# MCU.net
KiCad netlist of a schematic drawn in EasyEDA Pro
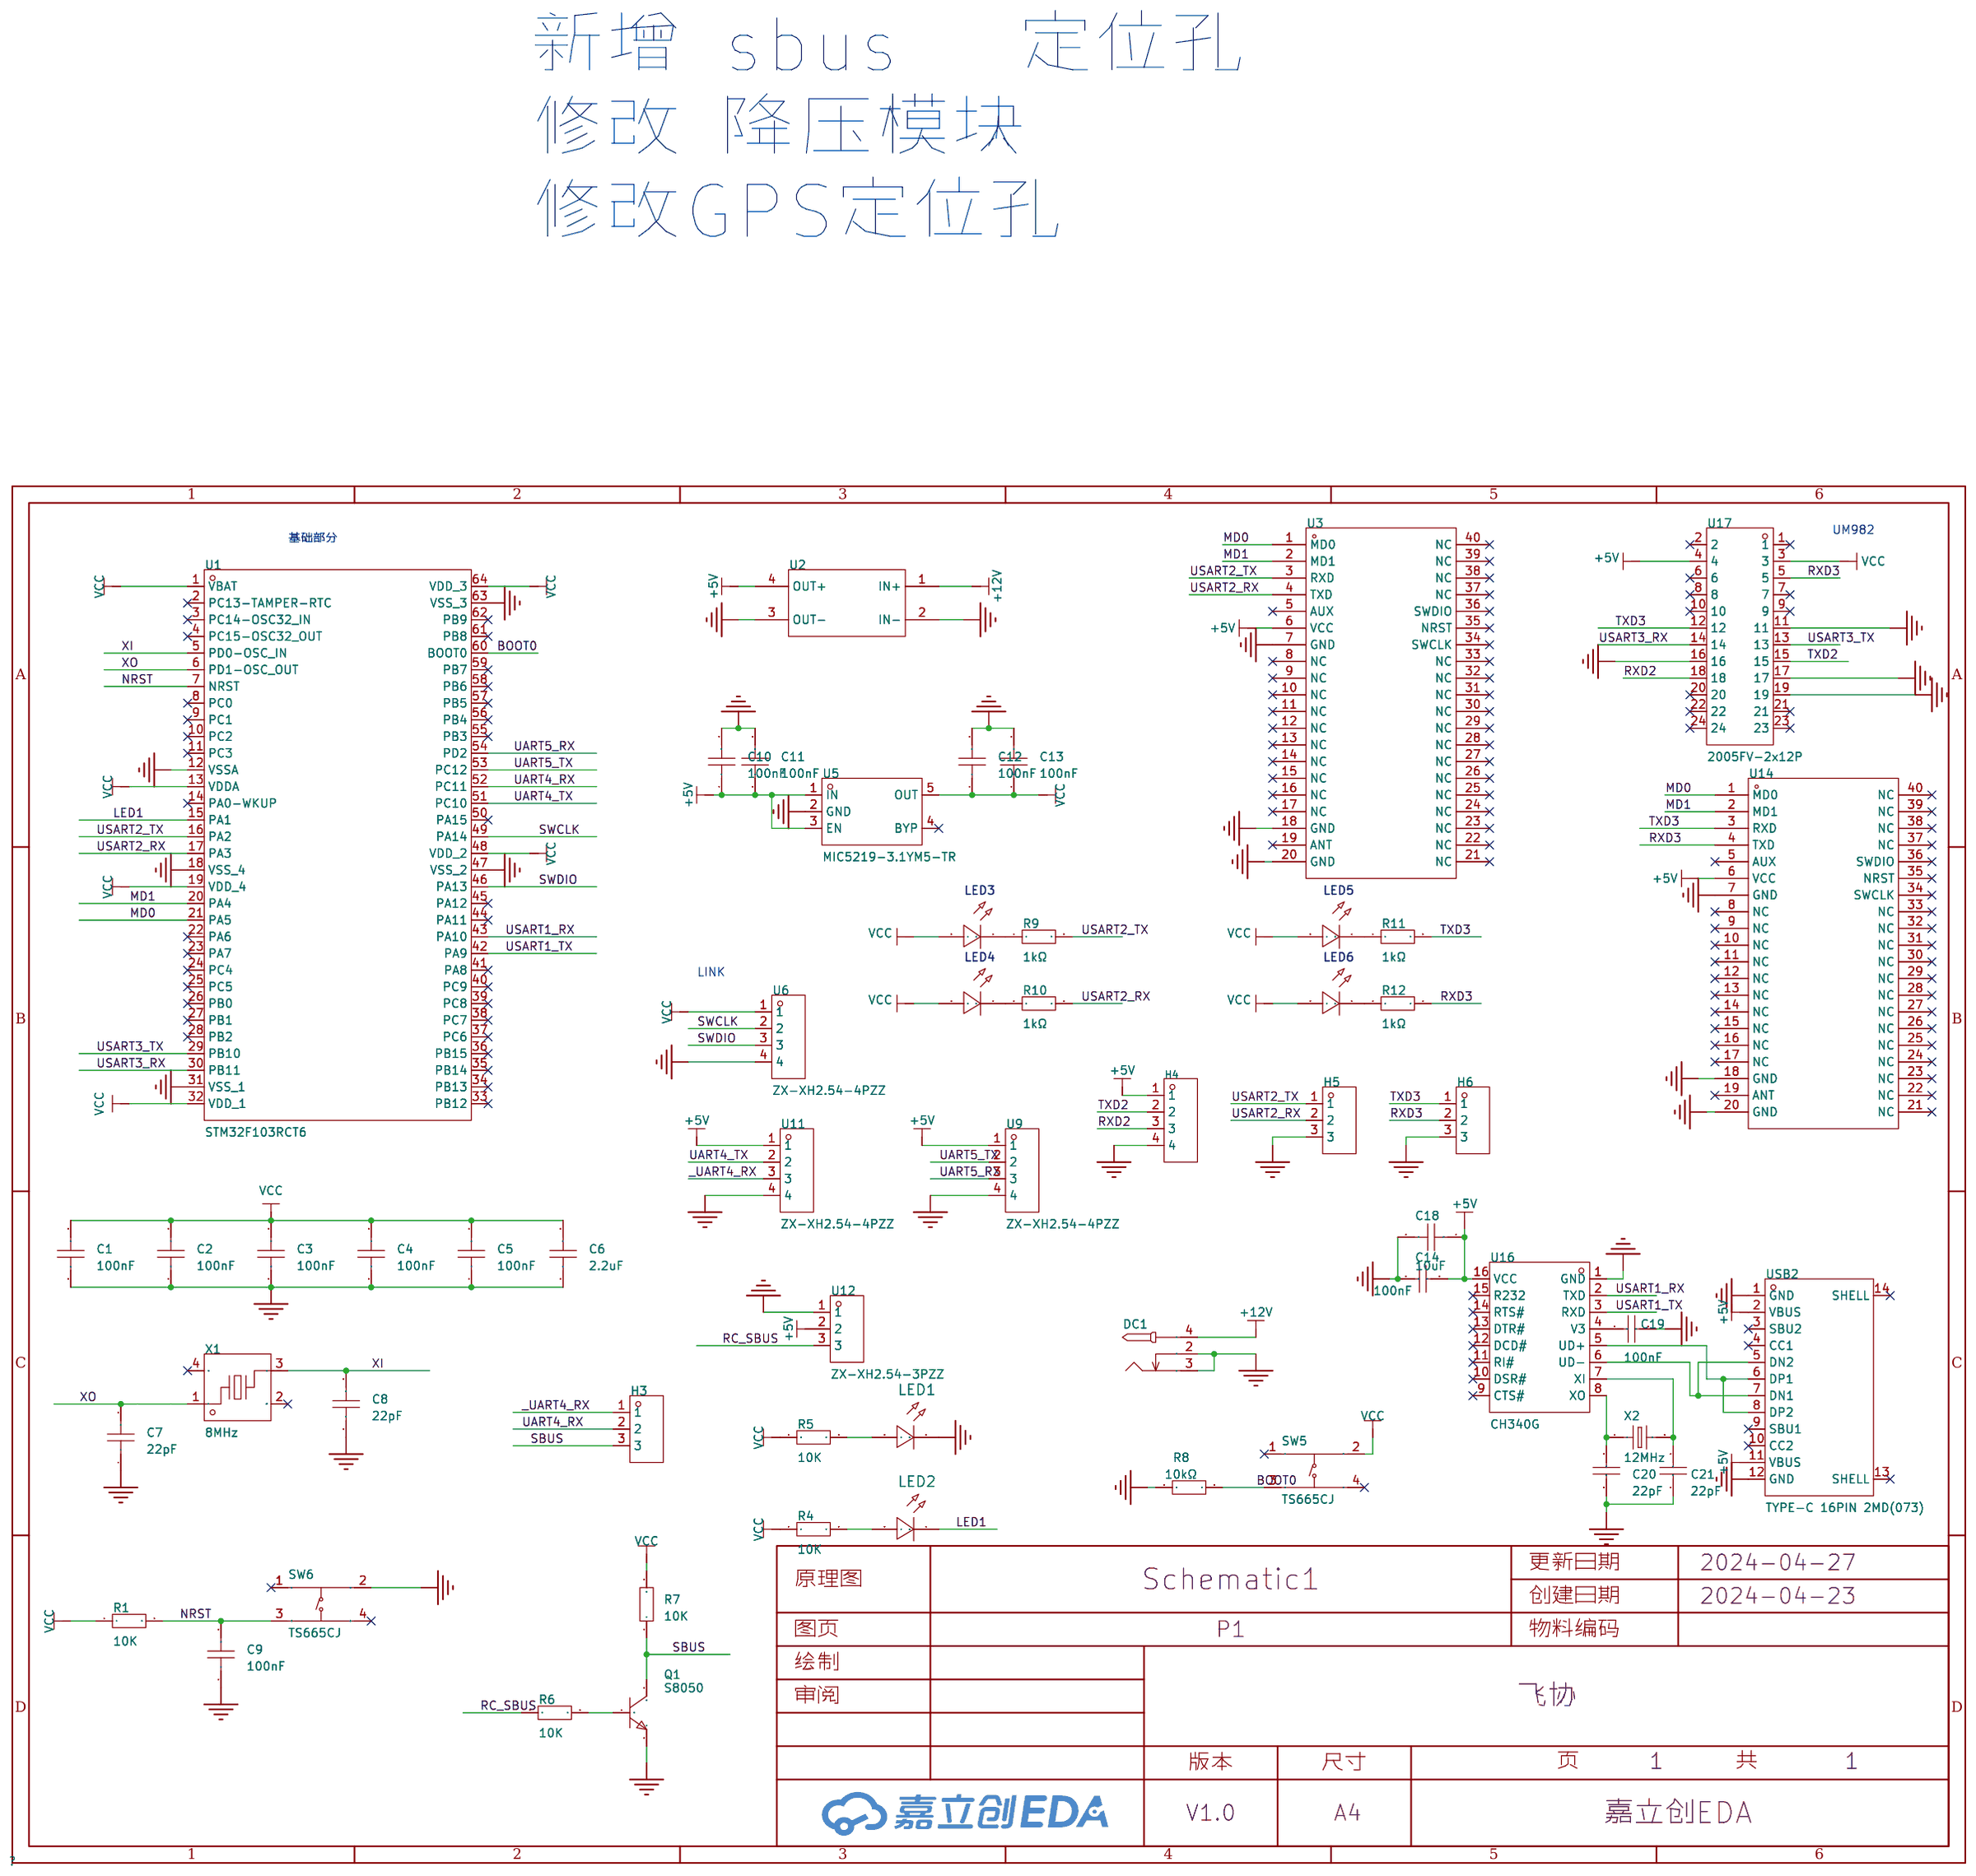
[diagram p0: schematic sheet]

(export (version "E")
  (design (tool "Eeschema 10.0.6"))
  (components
    (comp (ref "C1")
      (value "100nF")
      (footprint "easyedapro:C0603")
      (libsource (lib "easyedapro") (part "CapAcitance"))
    )
    (comp (ref "C2")
      (value "100nF")
      (footprint "easyedapro:C0603")
      (libsource (lib "easyedapro") (part "CapAcitance"))
    )
    (comp (ref "C3")
      (value "100nF")
      (footprint "easyedapro:C0603")
      (libsource (lib "easyedapro") (part "CapAcitance"))
    )
    (comp (ref "C4")
      (value "100nF")
      (footprint "easyedapro:C0603")
      (libsource (lib "easyedapro") (part "CapAcitance"))
    )
    (comp (ref "C5")
      (value "100nF")
      (footprint "easyedapro:C0603")
      (libsource (lib "easyedapro") (part "CapAcitance"))
    )
    (comp (ref "C6")
      (value "2.2uF")
      (footprint "easyedapro:C0603")
      (libsource (lib "easyedapro") (part "CapAcitance"))
    )
    (comp (ref "C7")
      (value "22pF")
      (footprint "easyedapro:C0603")
      (libsource (lib "easyedapro") (part "CapAcitance"))
    )
    (comp (ref "C8")
      (value "22pF")
      (footprint "easyedapro:C0603")
      (libsource (lib "easyedapro") (part "CapAcitance"))
    )
    (comp (ref "C9")
      (value "100nF")
      (footprint "easyedapro:C0603")
      (libsource (lib "easyedapro") (part "CapAcitance"))
    )
    (comp (ref "C10")
      (value "100nF")
      (footprint "easyedapro:C0603")
      (libsource (lib "easyedapro") (part "CapAcitance"))
    )
    (comp (ref "C11")
      (value "100nF")
      (footprint "easyedapro:C0603")
      (libsource (lib "easyedapro") (part "CapAcitance"))
    )
    (comp (ref "C12")
      (value "100nF")
      (footprint "easyedapro:C0603")
      (libsource (lib "easyedapro") (part "CapAcitance"))
    )
    (comp (ref "C13")
      (value "100nF")
      (footprint "easyedapro:C0603")
      (libsource (lib "easyedapro") (part "CapAcitance"))
    )
    (comp (ref "C14")
      (value "100nF")
      (footprint "easyedapro:C0603")
      (description "容值:100nF;精度:±10%;额定电压:50V;材质(温度系数):X7R;")
      (fields (field (name "Manufacturer Part") "0603B104K500NT") (field (name "Manufacturer") "FH(风华)"))
      (libsource (lib "easyedapro") (part "0603B104K500NT"))
    )
    (comp (ref "C18")
      (value "10uF")
      (footprint "easyedapro:C0603")
      (description "容值:10uF;精度:±20%;额定电压:25V;材质(温度系数):X5R;")
      (fields
        (field (name "Manufacturer Part") "CL10A106MA8NRNC")
        (field (name "Manufacturer") "SAMSUNG(三星)")
      )
      (libsource (lib "easyedapro") (part "CL10A106MA8NRNC"))
    )
    (comp (ref "C19")
      (value "100nF")
      (footprint "easyedapro:C0603")
      (description "容值:100nF;精度:±10%;额定电压:50V;材质(温度系数):X7R;")
      (fields (field (name "Manufacturer Part") "0603B104K500NT") (field (name "Manufacturer") "FH(风华)"))
      (libsource (lib "easyedapro") (part "0603B104K500NT"))
    )
    (comp (ref "C20")
      (value "22pF")
      (footprint "easyedapro:C0603")
      (description "容值:22pF;精度:±5%;额定电压:50V;材质(温度系数):NP0;")
      (fields
        (field (name "Manufacturer Part") "CC0603JRNPO9BN220")
        (field (name "Manufacturer") "YAGEO(国巨)")
      )
      (libsource (lib "easyedapro") (part "CC0603JRNPO9BN220"))
    )
    (comp (ref "C21")
      (value "22pF")
      (footprint "easyedapro:C0603")
      (description "容值:22pF;精度:±5%;额定电压:50V;材质(温度系数):NP0;")
      (fields
        (field (name "Manufacturer Part") "CC0603JRNPO9BN220")
        (field (name "Manufacturer") "YAGEO(国巨)")
      )
      (libsource (lib "easyedapro") (part "CC0603JRNPO9BN220"))
    )
    (comp (ref "DC1")
      (value "~")
      (footprint "easyedapro:DC-2.0")
      (libsource (lib "easyedapro") (part "DC电源接口"))
    )
    (comp (ref "H3")
      (value "~")
      (footprint "easyedapro:HDR-TH_3P-P2.54-V-M")
      (libsource (lib "easyedapro") (part "PZ254V-11-03P_C2937625"))
    )
    (comp (ref "H4")
      (value "~")
      (footprint "easyedapro:HDR-TH_4P-P2.54-V-M")
      (libsource (lib "easyedapro") (part "PZ254V-11-04P"))
    )
    (comp (ref "H5")
      (value "~")
      (footprint "easyedapro:HDR-TH_3P-P2.54-V-M")
      (libsource (lib "easyedapro") (part "PZ254V-11-03P_C2937625"))
    )
    (comp (ref "H6")
      (value "~")
      (footprint "easyedapro:HDR-TH_3P-P2.54-V-M")
      (libsource (lib "easyedapro") (part "PZ254V-11-03P_C2937625"))
    )
    (comp (ref "LED1")
      (value "~")
      (footprint "easyedapro:LED_0603")
      (libsource (lib "easyedapro") (part "LED_R"))
    )
    (comp (ref "LED2")
      (value "~")
      (footprint "easyedapro:LED_0603")
      (libsource (lib "easyedapro") (part "LED_R"))
    )
    (comp (ref "LED3")
      (value "~")
      (footprint "easyedapro:LED_0603")
      (libsource (lib "easyedapro") (part "LED_B"))
    )
    (comp (ref "LED4")
      (value "~")
      (footprint "easyedapro:LED_0603")
      (libsource (lib "easyedapro") (part "LED_B"))
    )
    (comp (ref "LED5")
      (value "~")
      (footprint "easyedapro:LED_0603")
      (libsource (lib "easyedapro") (part "LED_B"))
    )
    (comp (ref "LED6")
      (value "~")
      (footprint "easyedapro:LED_0603")
      (libsource (lib "easyedapro") (part "LED_B"))
    )
    (comp (ref "Q1")
      (value "S8050")
      (footprint "easyedapro:SOT-23-3_L2.9-W1.3-P1.90-LS2.4-BR")
      (description "晶体管类型:NPN;集电极电流(Ic):500mA;集射极击穿电压(Vceo):25V;功率(Pd):300mW;")
      (fields (field (name "Manufacturer") "YONGYUTAI(永裕泰)"))
      (libsource (lib "easyedapro") (part "S8050_C2891804"))
    )
    (comp (ref "R1") (value "10K") (footprint "easyedapro:R0603") (libsource (lib "easyedapro") (part "电阻")))
    (comp (ref "R4") (value "10K") (footprint "easyedapro:R0603") (libsource (lib "easyedapro") (part "电阻")))
    (comp (ref "R5") (value "10K") (footprint "easyedapro:R0603") (libsource (lib "easyedapro") (part "电阻")))
    (comp (ref "R6") (value "10K") (footprint "easyedapro:R0603") (libsource (lib "easyedapro") (part "电阻")))
    (comp (ref "R7") (value "10K") (footprint "easyedapro:R0603") (libsource (lib "easyedapro") (part "电阻")))
    (comp (ref "R8")
      (value "10kΩ")
      (footprint "easyedapro:R0603")
      (description "电阻类型:厚膜电阻;阻值:10kΩ;精度:±1%;功率:100mW;最大工作电压:75V;温度系数:±100ppm/°C;")
      (fields (field (name "Manufacturer Part") "RC0603FR-0710KL") (field (name "Manufacturer") "YAGEO(国巨)"))
      (libsource (lib "easyedapro") (part "RC0603FR-0710KL"))
    )
    (comp (ref "R9")
      (value "1kΩ")
      (footprint "easyedapro:R0603")
      (description "电阻类型:厚膜电阻;阻值:1kΩ;精度:±1%;功率:100mW;")
      (fields (field (name "Manufacturer Part") "RC0603FR-071KL") (field (name "Manufacturer") "YAGEO(国巨)"))
      (libsource (lib "easyedapro") (part "RC0603FR-071KL"))
    )
    (comp (ref "R10")
      (value "1kΩ")
      (footprint "easyedapro:R0603")
      (description "电阻类型:厚膜电阻;阻值:1kΩ;精度:±1%;功率:100mW;")
      (fields (field (name "Manufacturer Part") "RC0603FR-071KL") (field (name "Manufacturer") "YAGEO(国巨)"))
      (libsource (lib "easyedapro") (part "RC0603FR-071KL"))
    )
    (comp (ref "R11")
      (value "1kΩ")
      (footprint "easyedapro:R0603")
      (description "电阻类型:厚膜电阻;阻值:1kΩ;精度:±1%;功率:100mW;")
      (fields (field (name "Manufacturer Part") "RC0603FR-071KL") (field (name "Manufacturer") "YAGEO(国巨)"))
      (libsource (lib "easyedapro") (part "RC0603FR-071KL"))
    )
    (comp (ref "R12")
      (value "1kΩ")
      (footprint "easyedapro:R0603")
      (description "电阻类型:厚膜电阻;阻值:1kΩ;精度:±1%;功率:100mW;")
      (fields (field (name "Manufacturer Part") "RC0603FR-071KL") (field (name "Manufacturer") "YAGEO(国巨)"))
      (libsource (lib "easyedapro") (part "RC0603FR-071KL"))
    )
    (comp (ref "SW5")
      (value "TS665CJ")
      (footprint "easyedapro:SW-TH_4P-L6.0-W6.0-P4.50-LS6.5")
      (description "电路结构:单刀单掷;按钮形状:圆形按钮;安装方式:直插;开关长度:6mm;开关宽度:6mm;开关高度:5mm;触点电流:50mA;额定电压(DC):12V;带灯:-;机械寿命:-;")
      (fields (field (name "Manufacturer") "SHOU HAN(首韩)"))
      (libsource (lib "easyedapro") (part "TS665CJ"))
    )
    (comp (ref "SW6")
      (value "TS665CJ")
      (footprint "easyedapro:SW-TH_4P-L6.0-W6.0-P4.50-LS6.5")
      (description "电路结构:单刀单掷;按钮形状:圆形按钮;安装方式:直插;开关长度:6mm;开关宽度:6mm;开关高度:5mm;触点电流:50mA;额定电压(DC):12V;带灯:-;机械寿命:-;")
      (fields (field (name "Manufacturer") "SHOU HAN(首韩)"))
      (libsource (lib "easyedapro") (part "TS665CJ"))
    )
    (comp (ref "U1")
      (value "STM32F103RCT6")
      (fields (field (name "Manufacturer") "ST(意法半导体)"))
      (libsource (lib "easyedapro") (part "STM32F103RCT6"))
    )
    (comp (ref "U2")
      (value "~")
      (footprint "easyedapro:MP2482")
      (description "7-30V--5 V  5A")
      (libsource (lib "easyedapro") (part "MP2482"))
    )
    (comp (ref "U3") (value "~") (libsource (lib "easyedapro") (part "S26")))
    (comp (ref "U5")
      (value "MIC5219-3.1YM5-TR")
      (footprint "easyedapro:SOT-23-5_L2.9-W1.6-P0.95-LS2.8-BR")
      (fields (field (name "Manufacturer") "MICROCHIP(美国微芯)"))
      (libsource (lib "easyedapro") (part "MIC5219-3.1YM5-TR"))
    )
    (comp (ref "U6")
      (value "ZX-XH2.54-4PZZ")
      (footprint "easyedapro:CONN-TH_4P-P2.50_4PIN")
      (fields (field (name "Manufacturer") "Megastar(兆星)"))
      (libsource (lib "easyedapro") (part "ZX-XH2.54-4PZZ"))
    )
    (comp (ref "U9")
      (value "ZX-XH2.54-4PZZ")
      (footprint "easyedapro:CONN-TH_4P-P2.50_4PIN")
      (fields (field (name "Manufacturer") "Megastar(兆星)"))
      (libsource (lib "easyedapro") (part "ZX-XH2.54-4PZZ"))
    )
    (comp (ref "U11")
      (value "ZX-XH2.54-4PZZ")
      (footprint "easyedapro:CONN-TH_4P-P2.50_4PIN")
      (fields (field (name "Manufacturer") "Megastar(兆星)"))
      (libsource (lib "easyedapro") (part "ZX-XH2.54-4PZZ"))
    )
    (comp (ref "U12")
      (value "ZX-XH2.54-3PZZ")
      (footprint "easyedapro:CONN-TH_3P-P2.54_2501S-3P")
      (fields (field (name "Manufacturer") "Megastar(兆星)"))
      (libsource (lib "easyedapro") (part "ZX-XH2.54-3PZZ"))
    )
    (comp (ref "U14") (value "~") (libsource (lib "easyedapro") (part "S26")))
    (comp (ref "U16")
      (value "CH340G")
      (footprint "easyedapro:SOIC-16_L9.9-W3.9-P1.27-LS6.0-BL")
      (description "应用功能:收发器;接口协议:USB 2.0;数据速率:2Mbps;")
      (fields (field (name "Manufacturer") "WCH(南京沁恒)"))
      (libsource (lib "easyedapro") (part "CH340G"))
    )
    (comp (ref "U17")
      (value "2005FV-2x12P")
      (footprint "easyedapro:HDR-TH_24P-P2.00-V-F-R2-C12-S2.00")
      (fields (field (name "Manufacturer") "HanElectricity(瀚源)"))
      (libsource (lib "easyedapro") (part "2005FV-2X12P"))
    )
    (comp (ref "USB2")
      (value "TYPE-C 16PIN 2MD(073)")
      (footprint "easyedapro:USB-C-SMD_TYPE-C-6PIN-2MD-073")
      (description "连接器类型:Type-C;标准:-;公母:母;端口数量:1;触点数量:16P;安装方式:卧贴;额定电流 - 电源:5A;工作温度范围:-25°C~+85°C;")
      (fields (field (name "Manufacturer") "SHOU HAN(首韩)"))
      (libsource (lib "easyedapro") (part "TYPE-C 16PIN 2MD(073)"))
    )
    (comp (ref "X1")
      (value "8MHz")
      (footprint "easyedapro:OSC-SMD_4P-L3.2-W2.5-BL")
      (description "晶振类型:贴片无源晶振;频率:8MHz;常温频差:±10ppm;负载电容:12pF;频率稳定度(全温):±30ppm;")
      (fields (field (name "Manufacturer Part") "X32258MOB4SI") (field (name "Manufacturer") "YXC(扬兴晶振)"))
      (libsource (lib "easyedapro") (part "X32258MOB4SI"))
    )
    (comp (ref "X2")
      (value "12MHz")
      (footprint "easyedapro:HC-49US_L11.5-W4.5-P4.88")
      (description "晶振类型:直插晶振;频率:12MHz;常温频差:±30ppm;外接负载电容:20pF;频率稳定度(全温):±30ppm;")
      (fields (field (name "Manufacturer Part") "TAXD12M2GLFBET2T") (field (name "Manufacturer") "YJX(雅晶鑫)"))
      (libsource (lib "easyedapro") (part "HC-49S12MHZ20PF30PPM"))
    )
  )
  (nets
    (net (code "1") (name "+5V") (class "Default")
      (node (ref "C10") (pin "1") (pinfunction "1_1") (pintype "input"))
      (node (ref "C11") (pin "1") (pinfunction "1_1") (pintype "input"))
      (node (ref "C14") (pin "1") (pinfunction "1_1") (pintype "input"))
      (node (ref "C18") (pin "1") (pinfunction "1_1") (pintype "unspecified"))
      (node (ref "H4") (pin "1") (pinfunction "1_1") (pintype "input"))
      (node (ref "U11") (pin "1") (pinfunction "1_1") (pintype "unspecified"))
      (node (ref "U12") (pin "2") (pinfunction "2_2") (pintype "unspecified"))
      (node (ref "U14") (pin "6") (pinfunction "VCC_6") (pintype "input"))
      (node (ref "U16") (pin "16") (pinfunction "VCC_16") (pintype "unspecified"))
      (node (ref "U17") (pin "4") (pinfunction "4_4") (pintype "unspecified"))
      (node (ref "U2") (pin "4") (pinfunction "OUT+_4") (pintype "output"))
      (node (ref "U3") (pin "6") (pinfunction "VCC_6") (pintype "input"))
      (node (ref "U5") (pin "1") (pinfunction "IN_1") (pintype "input"))
      (node (ref "U5") (pin "3") (pinfunction "EN_3") (pintype "input"))
      (node (ref "U9") (pin "1") (pinfunction "1_1") (pintype "unspecified"))
      (node (ref "USB2") (pin "11") (pinfunction "VBUS_11") (pintype "unspecified"))
      (node (ref "USB2") (pin "2") (pinfunction "VBUS_2") (pintype "unspecified"))
    )
    (net (code "2") (name "+12V") (class "Default")
      (node (ref "DC1") (pin "4") (pinfunction "4_4") (pintype "input"))
      (node (ref "U2") (pin "1") (pinfunction "IN+_1") (pintype "input"))
    )
    (net (code "3") (name "/BOOT0") (class "Default")
      (node (ref "R8") (pin "2") (pinfunction "2_2") (pintype "input"))
      (node (ref "SW5") (pin "3") (pinfunction "C_3") (pintype "unspecified"))
      (node (ref "U1") (pin "60") (pinfunction "BOOT0_60") (pintype "unspecified"))
    )
    (net (code "4") (name "/LED1") (class "Default")
      (node (ref "LED2") (pin "1") (pinfunction "C_1") (pintype "input"))
      (node (ref "U1") (pin "15") (pinfunction "PA1_15") (pintype "unspecified"))
    )
    (net (code "5") (name "/MD0") (class "Default")
      (node (ref "U1") (pin "21") (pinfunction "PA5_21") (pintype "unspecified"))
      (node (ref "U14") (pin "1") (pinfunction "MD0_1") (pintype "input"))
      (node (ref "U3") (pin "1") (pinfunction "MD0_1") (pintype "input"))
    )
    (net (code "6") (name "/MD1") (class "Default")
      (node (ref "U1") (pin "20") (pinfunction "PA4_20") (pintype "unspecified"))
      (node (ref "U14") (pin "2") (pinfunction "MD1_2") (pintype "input"))
      (node (ref "U3") (pin "2") (pinfunction "MD1_2") (pintype "input"))
    )
    (net (code "7") (name "/NRST") (class "Default")
      (node (ref "C9") (pin "2") (pinfunction "2_2") (pintype "input"))
      (node (ref "R1") (pin "2") (pinfunction "2_2") (pintype "input"))
      (node (ref "SW6") (pin "3") (pinfunction "C_3") (pintype "unspecified"))
      (node (ref "U1") (pin "7") (pinfunction "NRST_7") (pintype "unspecified"))
    )
    (net (code "8") (name "/RC_SBUS") (class "Default")
      (node (ref "R6") (pin "1") (pinfunction "1_1") (pintype "input"))
      (node (ref "U12") (pin "3") (pinfunction "3_3") (pintype "unspecified"))
    )
    (net (code "9") (name "/RXD2") (class "Default")
      (node (ref "H4") (pin "3") (pinfunction "3_3") (pintype "input"))
      (node (ref "U17") (pin "18") (pinfunction "18_18") (pintype "unspecified"))
    )
    (net (code "10") (name "/RXD3") (class "Default")
      (node (ref "H6") (pin "2") (pinfunction "2_2") (pintype "input"))
      (node (ref "R12") (pin "2") (pinfunction "2_2") (pintype "input"))
      (node (ref "U14") (pin "4") (pinfunction "TXD_4") (pintype "input"))
      (node (ref "U17") (pin "5") (pinfunction "5_5") (pintype "unspecified"))
    )
    (net (code "11") (name "/SBUS") (class "Default")
      (node (ref "H3") (pin "3") (pinfunction "3_3") (pintype "input"))
      (node (ref "Q1") (pin "3") (pinfunction "C_3") (pintype "unspecified"))
      (node (ref "R7") (pin "1") (pinfunction "1_1") (pintype "input"))
    )
    (net (code "12") (name "/SWCLK") (class "Default")
      (node (ref "U1") (pin "49") (pinfunction "PA14_49") (pintype "unspecified"))
      (node (ref "U6") (pin "2") (pinfunction "2_2") (pintype "unspecified"))
    )
    (net (code "13") (name "/SWDIO") (class "Default")
      (node (ref "U1") (pin "46") (pinfunction "PA13_46") (pintype "unspecified"))
      (node (ref "U6") (pin "3") (pinfunction "3_3") (pintype "unspecified"))
    )
    (net (code "14") (name "/TXD2") (class "Default")
      (node (ref "H4") (pin "2") (pinfunction "2_2") (pintype "input"))
      (node (ref "U17") (pin "15") (pinfunction "15_15") (pintype "unspecified"))
    )
    (net (code "15") (name "/TXD3") (class "Default")
      (node (ref "H6") (pin "1") (pinfunction "1_1") (pintype "input"))
      (node (ref "R11") (pin "2") (pinfunction "2_2") (pintype "input"))
      (node (ref "U14") (pin "3") (pinfunction "RXD_3") (pintype "input"))
      (node (ref "U17") (pin "12") (pinfunction "12_12") (pintype "unspecified"))
    )
    (net (code "16") (name "/UART4_RX") (class "Default")
      (node (ref "H3") (pin "2") (pinfunction "2_2") (pintype "input"))
      (node (ref "U1") (pin "52") (pinfunction "PC11_52") (pintype "unspecified"))
    )
    (net (code "17") (name "/UART4_TX") (class "Default")
      (node (ref "U1") (pin "51") (pinfunction "PC10_51") (pintype "unspecified"))
      (node (ref "U11") (pin "2") (pinfunction "2_2") (pintype "unspecified"))
    )
    (net (code "18") (name "/UART5_RX") (class "Default")
      (node (ref "U1") (pin "54") (pinfunction "PD2_54") (pintype "unspecified"))
      (node (ref "U9") (pin "3") (pinfunction "3_3") (pintype "unspecified"))
    )
    (net (code "19") (name "/UART5_TX") (class "Default")
      (node (ref "U1") (pin "53") (pinfunction "PC12_53") (pintype "unspecified"))
      (node (ref "U9") (pin "2") (pinfunction "2_2") (pintype "unspecified"))
    )
    (net (code "20") (name "/USART1_RX") (class "Default")
      (node (ref "U1") (pin "43") (pinfunction "PA10_43") (pintype "unspecified"))
      (node (ref "U16") (pin "2") (pinfunction "TXD_2") (pintype "unspecified"))
    )
    (net (code "21") (name "/USART1_TX") (class "Default")
      (node (ref "U1") (pin "42") (pinfunction "PA9_42") (pintype "unspecified"))
      (node (ref "U16") (pin "3") (pinfunction "RXD_3") (pintype "unspecified"))
    )
    (net (code "22") (name "/USART2_RX") (class "Default")
      (node (ref "H5") (pin "2") (pinfunction "2_2") (pintype "input"))
      (node (ref "R10") (pin "2") (pinfunction "2_2") (pintype "input"))
      (node (ref "U1") (pin "17") (pinfunction "PA3_17") (pintype "unspecified"))
      (node (ref "U3") (pin "4") (pinfunction "TXD_4") (pintype "input"))
    )
    (net (code "23") (name "/USART2_TX") (class "Default")
      (node (ref "H5") (pin "1") (pinfunction "1_1") (pintype "input"))
      (node (ref "R9") (pin "2") (pinfunction "2_2") (pintype "input"))
      (node (ref "U1") (pin "16") (pinfunction "PA2_16") (pintype "unspecified"))
      (node (ref "U3") (pin "3") (pinfunction "RXD_3") (pintype "input"))
    )
    (net (code "24") (name "/USART3_RX") (class "Default")
      (node (ref "U1") (pin "30") (pinfunction "PB11_30") (pintype "unspecified"))
      (node (ref "U17") (pin "14") (pinfunction "14_14") (pintype "unspecified"))
    )
    (net (code "25") (name "/USART3_TX") (class "Default")
      (node (ref "U1") (pin "29") (pinfunction "PB10_29") (pintype "unspecified"))
      (node (ref "U17") (pin "13") (pinfunction "13_13") (pintype "unspecified"))
    )
    (net (code "26") (name "/XI") (class "Default")
      (node (ref "C8") (pin "2") (pinfunction "2_2") (pintype "input"))
      (node (ref "U1") (pin "5") (pinfunction "PD0-OSC_IN_5") (pintype "unspecified"))
      (node (ref "X1") (pin "3") (pinfunction "3_3") (pintype "input"))
    )
    (net (code "27") (name "/XO") (class "Default")
      (node (ref "C7") (pin "2") (pinfunction "2_2") (pintype "input"))
      (node (ref "U1") (pin "6") (pinfunction "PD1-OSC_OUT_6") (pintype "unspecified"))
      (node (ref "X1") (pin "1") (pinfunction "1_1") (pintype "input"))
    )
    (net (code "28") (name "/_UART4_RX") (class "Default")
      (node (ref "H3") (pin "1") (pinfunction "1_1") (pintype "input"))
      (node (ref "U11") (pin "3") (pinfunction "3_3") (pintype "unspecified"))
    )
    (net (code "29") (name "GND") (class "Default")
      (node (ref "C1") (pin "1") (pinfunction "1_1") (pintype "input"))
      (node (ref "C10") (pin "2") (pinfunction "2_2") (pintype "input"))
      (node (ref "C11") (pin "2") (pinfunction "2_2") (pintype "input"))
      (node (ref "C12") (pin "2") (pinfunction "2_2") (pintype "input"))
      (node (ref "C13") (pin "2") (pinfunction "2_2") (pintype "input"))
      (node (ref "C14") (pin "2") (pinfunction "2_2") (pintype "input"))
      (node (ref "C18") (pin "2") (pinfunction "2_2") (pintype "unspecified"))
      (node (ref "C19") (pin "1") (pinfunction "1_1") (pintype "input"))
      (node (ref "C2") (pin "1") (pinfunction "1_1") (pintype "input"))
      (node (ref "C20") (pin "1") (pinfunction "1_1") (pintype "input"))
      (node (ref "C21") (pin "1") (pinfunction "1_1") (pintype "input"))
      (node (ref "C3") (pin "1") (pinfunction "1_1") (pintype "input"))
      (node (ref "C4") (pin "1") (pinfunction "1_1") (pintype "input"))
      (node (ref "C5") (pin "1") (pinfunction "1_1") (pintype "input"))
      (node (ref "C6") (pin "1") (pinfunction "1_1") (pintype "input"))
      (node (ref "C7") (pin "1") (pinfunction "1_1") (pintype "input"))
      (node (ref "C8") (pin "1") (pinfunction "1_1") (pintype "input"))
      (node (ref "C9") (pin "1") (pinfunction "1_1") (pintype "input"))
      (node (ref "DC1") (pin "2") (pinfunction "2_2") (pintype "input"))
      (node (ref "DC1") (pin "3") (pinfunction "3_3") (pintype "input"))
      (node (ref "H4") (pin "4") (pinfunction "4_4") (pintype "input"))
      (node (ref "H5") (pin "3") (pinfunction "3_3") (pintype "input"))
      (node (ref "H6") (pin "3") (pinfunction "3_3") (pintype "input"))
      (node (ref "LED1") (pin "1") (pinfunction "C_1") (pintype "input"))
      (node (ref "Q1") (pin "2") (pinfunction "E_2") (pintype "unspecified"))
      (node (ref "R8") (pin "1") (pinfunction "1_1") (pintype "input"))
      (node (ref "SW6") (pin "2") (pinfunction "B_2") (pintype "unspecified"))
      (node (ref "U1") (pin "12") (pinfunction "VSSA_12") (pintype "unspecified"))
      (node (ref "U1") (pin "18") (pinfunction "VSS_4_18") (pintype "unspecified"))
      (node (ref "U1") (pin "31") (pinfunction "VSS_1_31") (pintype "unspecified"))
      (node (ref "U1") (pin "47") (pinfunction "VSS_2_47") (pintype "unspecified"))
      (node (ref "U1") (pin "63") (pinfunction "VSS_3_63") (pintype "unspecified"))
      (node (ref "U11") (pin "4") (pinfunction "4_4") (pintype "unspecified"))
      (node (ref "U12") (pin "1") (pinfunction "1_1") (pintype "unspecified"))
      (node (ref "U14") (pin "18") (pinfunction "GND_18") (pintype "input"))
      (node (ref "U14") (pin "20") (pinfunction "GND_20") (pintype "input"))
      (node (ref "U14") (pin "7") (pinfunction "GND_7") (pintype "input"))
      (node (ref "U16") (pin "1") (pinfunction "GND_1") (pintype "unspecified"))
      (node (ref "U17") (pin "11") (pinfunction "11_11") (pintype "unspecified"))
      (node (ref "U17") (pin "16") (pinfunction "16_16") (pintype "unspecified"))
      (node (ref "U17") (pin "17") (pinfunction "17_17") (pintype "unspecified"))
      (node (ref "U17") (pin "19") (pinfunction "19_19") (pintype "unspecified"))
      (node (ref "U2") (pin "2") (pinfunction "IN-_2") (pintype "input"))
      (node (ref "U2") (pin "3") (pinfunction "OUT-_3") (pintype "output"))
      (node (ref "U3") (pin "18") (pinfunction "GND_18") (pintype "input"))
      (node (ref "U3") (pin "20") (pinfunction "GND_20") (pintype "input"))
      (node (ref "U3") (pin "7") (pinfunction "GND_7") (pintype "input"))
      (node (ref "U5") (pin "2") (pinfunction "GND_2") (pintype "input"))
      (node (ref "U6") (pin "4") (pinfunction "4_4") (pintype "unspecified"))
      (node (ref "U9") (pin "4") (pinfunction "4_4") (pintype "unspecified"))
      (node (ref "USB2") (pin "1") (pinfunction "GND_1") (pintype "unspecified"))
      (node (ref "USB2") (pin "12") (pinfunction "GND_12") (pintype "unspecified"))
    )
    (net (code "30") (name "Net-(LED1-A)") (class "Default")
      (node (ref "LED1") (pin "2") (pinfunction "A_2") (pintype "input"))
      (node (ref "R5") (pin "2") (pinfunction "2_2") (pintype "input"))
    )
    (net (code "31") (name "Net-(LED2-A)") (class "Default")
      (node (ref "LED2") (pin "2") (pinfunction "A_2") (pintype "input"))
      (node (ref "R4") (pin "2") (pinfunction "2_2") (pintype "input"))
    )
    (net (code "32") (name "Net-(LED3-C)") (class "Default")
      (node (ref "LED3") (pin "1") (pinfunction "C_1") (pintype "input"))
      (node (ref "R9") (pin "1") (pinfunction "1_1") (pintype "input"))
    )
    (net (code "33") (name "Net-(LED4-C)") (class "Default")
      (node (ref "LED4") (pin "1") (pinfunction "C_1") (pintype "input"))
      (node (ref "R10") (pin "1") (pinfunction "1_1") (pintype "input"))
    )
    (net (code "34") (name "Net-(LED5-C)") (class "Default")
      (node (ref "LED5") (pin "1") (pinfunction "C_1") (pintype "input"))
      (node (ref "R11") (pin "1") (pinfunction "1_1") (pintype "input"))
    )
    (net (code "35") (name "Net-(LED6-C)") (class "Default")
      (node (ref "LED6") (pin "1") (pinfunction "C_1") (pintype "input"))
      (node (ref "R12") (pin "1") (pinfunction "1_1") (pintype "input"))
    )
    (net (code "36") (name "Net-(Q1-B)") (class "Default")
      (node (ref "Q1") (pin "1") (pinfunction "B_1") (pintype "unspecified"))
      (node (ref "R6") (pin "2") (pinfunction "2_2") (pintype "input"))
    )
    (net (code "37") (name "Net-(U16-UD+)") (class "Default")
      (node (ref "U16") (pin "5") (pinfunction "UD+_5") (pintype "unspecified"))
      (node (ref "USB2") (pin "6") (pinfunction "DP1_6") (pintype "unspecified"))
      (node (ref "USB2") (pin "8") (pinfunction "DP2_8") (pintype "unspecified"))
    )
    (net (code "38") (name "Net-(U16-UD-)") (class "Default")
      (node (ref "U16") (pin "6") (pinfunction "UD-_6") (pintype "unspecified"))
      (node (ref "USB2") (pin "5") (pinfunction "DN2_5") (pintype "unspecified"))
      (node (ref "USB2") (pin "7") (pinfunction "DN1_7") (pintype "unspecified"))
    )
    (net (code "39") (name "Net-(U16-V3)") (class "Default")
      (node (ref "C19") (pin "2") (pinfunction "2_2") (pintype "input"))
      (node (ref "U16") (pin "4") (pinfunction "V3_4") (pintype "unspecified"))
    )
    (net (code "40") (name "Net-(U16-XI)") (class "Default")
      (node (ref "C21") (pin "2") (pinfunction "2_2") (pintype "input"))
      (node (ref "U16") (pin "7") (pinfunction "XI_7") (pintype "unspecified"))
      (node (ref "X2") (pin "2") (pinfunction "2_2") (pintype "unspecified"))
    )
    (net (code "41") (name "Net-(U16-XO)") (class "Default")
      (node (ref "C20") (pin "2") (pinfunction "2_2") (pintype "input"))
      (node (ref "U16") (pin "8") (pinfunction "XO_8") (pintype "unspecified"))
      (node (ref "X2") (pin "1") (pinfunction "1_1") (pintype "unspecified"))
    )
    (net (code "42") (name "VCC") (class "Default")
      (node (ref "C1") (pin "2") (pinfunction "2_2") (pintype "input"))
      (node (ref "C12") (pin "1") (pinfunction "1_1") (pintype "input"))
      (node (ref "C13") (pin "1") (pinfunction "1_1") (pintype "input"))
      (node (ref "C2") (pin "2") (pinfunction "2_2") (pintype "input"))
      (node (ref "C3") (pin "2") (pinfunction "2_2") (pintype "input"))
      (node (ref "C4") (pin "2") (pinfunction "2_2") (pintype "input"))
      (node (ref "C5") (pin "2") (pinfunction "2_2") (pintype "input"))
      (node (ref "C6") (pin "2") (pinfunction "2_2") (pintype "input"))
      (node (ref "LED3") (pin "2") (pinfunction "A_2") (pintype "input"))
      (node (ref "LED4") (pin "2") (pinfunction "A_2") (pintype "input"))
      (node (ref "LED5") (pin "2") (pinfunction "A_2") (pintype "input"))
      (node (ref "LED6") (pin "2") (pinfunction "A_2") (pintype "input"))
      (node (ref "R1") (pin "1") (pinfunction "1_1") (pintype "input"))
      (node (ref "R4") (pin "1") (pinfunction "1_1") (pintype "input"))
      (node (ref "R5") (pin "1") (pinfunction "1_1") (pintype "input"))
      (node (ref "R7") (pin "2") (pinfunction "2_2") (pintype "input"))
      (node (ref "SW5") (pin "2") (pinfunction "B_2") (pintype "unspecified"))
      (node (ref "U1") (pin "1") (pinfunction "VBAT_1") (pintype "unspecified"))
      (node (ref "U1") (pin "13") (pinfunction "VDDA_13") (pintype "unspecified"))
      (node (ref "U1") (pin "19") (pinfunction "VDD_4_19") (pintype "unspecified"))
      (node (ref "U1") (pin "32") (pinfunction "VDD_1_32") (pintype "unspecified"))
      (node (ref "U1") (pin "48") (pinfunction "VDD_2_48") (pintype "unspecified"))
      (node (ref "U1") (pin "64") (pinfunction "VDD_3_64") (pintype "unspecified"))
      (node (ref "U17") (pin "3") (pinfunction "3_3") (pintype "unspecified"))
      (node (ref "U5") (pin "5") (pinfunction "OUT_5") (pintype "input"))
      (node (ref "U6") (pin "1") (pinfunction "1_1") (pintype "unspecified"))
    )
    (net (code "43") (name "unconnected-(SW5-A-Pad1)") (class "Default")
      (node (ref "SW5") (pin "1") (pinfunction "A_1") (pintype "unspecified+no_connect"))
    )
    (net (code "44") (name "unconnected-(SW5-D-Pad4)") (class "Default")
      (node (ref "SW5") (pin "4") (pinfunction "D_4") (pintype "unspecified+no_connect"))
    )
    (net (code "45") (name "unconnected-(SW6-A-Pad1)") (class "Default")
      (node (ref "SW6") (pin "1") (pinfunction "A_1") (pintype "unspecified+no_connect"))
    )
    (net (code "46") (name "unconnected-(SW6-D-Pad4)") (class "Default")
      (node (ref "SW6") (pin "4") (pinfunction "D_4") (pintype "unspecified+no_connect"))
    )
    (net (code "47") (name "unconnected-(U1-PA0-WKUP-Pad14)") (class "Default")
      (node (ref "U1") (pin "14") (pinfunction "PA0-WKUP_14") (pintype "unspecified+no_connect"))
    )
    (net (code "48") (name "unconnected-(U1-PA6-Pad22)") (class "Default")
      (node (ref "U1") (pin "22") (pinfunction "PA6_22") (pintype "unspecified+no_connect"))
    )
    (net (code "49") (name "unconnected-(U1-PA7-Pad23)") (class "Default")
      (node (ref "U1") (pin "23") (pinfunction "PA7_23") (pintype "unspecified+no_connect"))
    )
    (net (code "50") (name "unconnected-(U1-PA8-Pad41)") (class "Default")
      (node (ref "U1") (pin "41") (pinfunction "PA8_41") (pintype "unspecified+no_connect"))
    )
    (net (code "51") (name "unconnected-(U1-PA11-Pad44)") (class "Default")
      (node (ref "U1") (pin "44") (pinfunction "PA11_44") (pintype "unspecified+no_connect"))
    )
    (net (code "52") (name "unconnected-(U1-PA12-Pad45)") (class "Default")
      (node (ref "U1") (pin "45") (pinfunction "PA12_45") (pintype "unspecified+no_connect"))
    )
    (net (code "53") (name "unconnected-(U1-PA15-Pad50)") (class "Default")
      (node (ref "U1") (pin "50") (pinfunction "PA15_50") (pintype "unspecified+no_connect"))
    )
    (net (code "54") (name "unconnected-(U1-PB0-Pad26)") (class "Default")
      (node (ref "U1") (pin "26") (pinfunction "PB0_26") (pintype "unspecified+no_connect"))
    )
    (net (code "55") (name "unconnected-(U1-PB1-Pad27)") (class "Default")
      (node (ref "U1") (pin "27") (pinfunction "PB1_27") (pintype "unspecified+no_connect"))
    )
    (net (code "56") (name "unconnected-(U1-PB2-Pad28)") (class "Default")
      (node (ref "U1") (pin "28") (pinfunction "PB2_28") (pintype "unspecified+no_connect"))
    )
    (net (code "57") (name "unconnected-(U1-PB3-Pad55)") (class "Default")
      (node (ref "U1") (pin "55") (pinfunction "PB3_55") (pintype "unspecified+no_connect"))
    )
    (net (code "58") (name "unconnected-(U1-PB4-Pad56)") (class "Default")
      (node (ref "U1") (pin "56") (pinfunction "PB4_56") (pintype "unspecified+no_connect"))
    )
    (net (code "59") (name "unconnected-(U1-PB5-Pad57)") (class "Default")
      (node (ref "U1") (pin "57") (pinfunction "PB5_57") (pintype "unspecified+no_connect"))
    )
    (net (code "60") (name "unconnected-(U1-PB6-Pad58)") (class "Default")
      (node (ref "U1") (pin "58") (pinfunction "PB6_58") (pintype "unspecified+no_connect"))
    )
    (net (code "61") (name "unconnected-(U1-PB7-Pad59)") (class "Default")
      (node (ref "U1") (pin "59") (pinfunction "PB7_59") (pintype "unspecified+no_connect"))
    )
    (net (code "62") (name "unconnected-(U1-PB8-Pad61)") (class "Default")
      (node (ref "U1") (pin "61") (pinfunction "PB8_61") (pintype "unspecified+no_connect"))
    )
    (net (code "63") (name "unconnected-(U1-PB9-Pad62)") (class "Default")
      (node (ref "U1") (pin "62") (pinfunction "PB9_62") (pintype "unspecified+no_connect"))
    )
    (net (code "64") (name "unconnected-(U1-PB12-Pad33)") (class "Default")
      (node (ref "U1") (pin "33") (pinfunction "PB12_33") (pintype "unspecified+no_connect"))
    )
    (net (code "65") (name "unconnected-(U1-PB13-Pad34)") (class "Default")
      (node (ref "U1") (pin "34") (pinfunction "PB13_34") (pintype "unspecified+no_connect"))
    )
    (net (code "66") (name "unconnected-(U1-PB14-Pad35)") (class "Default")
      (node (ref "U1") (pin "35") (pinfunction "PB14_35") (pintype "unspecified+no_connect"))
    )
    (net (code "67") (name "unconnected-(U1-PB15-Pad36)") (class "Default")
      (node (ref "U1") (pin "36") (pinfunction "PB15_36") (pintype "unspecified+no_connect"))
    )
    (net (code "68") (name "unconnected-(U1-PC0-Pad8)") (class "Default")
      (node (ref "U1") (pin "8") (pinfunction "PC0_8") (pintype "unspecified+no_connect"))
    )
    (net (code "69") (name "unconnected-(U1-PC1-Pad9)") (class "Default")
      (node (ref "U1") (pin "9") (pinfunction "PC1_9") (pintype "unspecified+no_connect"))
    )
    (net (code "70") (name "unconnected-(U1-PC2-Pad10)") (class "Default")
      (node (ref "U1") (pin "10") (pinfunction "PC2_10") (pintype "unspecified+no_connect"))
    )
    (net (code "71") (name "unconnected-(U1-PC3-Pad11)") (class "Default")
      (node (ref "U1") (pin "11") (pinfunction "PC3_11") (pintype "unspecified+no_connect"))
    )
    (net (code "72") (name "unconnected-(U1-PC4-Pad24)") (class "Default")
      (node (ref "U1") (pin "24") (pinfunction "PC4_24") (pintype "unspecified+no_connect"))
    )
    (net (code "73") (name "unconnected-(U1-PC5-Pad25)") (class "Default")
      (node (ref "U1") (pin "25") (pinfunction "PC5_25") (pintype "unspecified+no_connect"))
    )
    (net (code "74") (name "unconnected-(U1-PC6-Pad37)") (class "Default")
      (node (ref "U1") (pin "37") (pinfunction "PC6_37") (pintype "unspecified+no_connect"))
    )
    (net (code "75") (name "unconnected-(U1-PC7-Pad38)") (class "Default")
      (node (ref "U1") (pin "38") (pinfunction "PC7_38") (pintype "unspecified+no_connect"))
    )
    (net (code "76") (name "unconnected-(U1-PC8-Pad39)") (class "Default")
      (node (ref "U1") (pin "39") (pinfunction "PC8_39") (pintype "unspecified+no_connect"))
    )
    (net (code "77") (name "unconnected-(U1-PC9-Pad40)") (class "Default")
      (node (ref "U1") (pin "40") (pinfunction "PC9_40") (pintype "unspecified+no_connect"))
    )
    (net (code "78") (name "unconnected-(U1-PC13-TAMPER-RTC-Pad2)") (class "Default")
      (node (ref "U1") (pin "2") (pinfunction "PC13-TAMPER-RTC_2") (pintype "unspecified+no_connect"))
    )
    (net (code "79") (name "unconnected-(U1-PC14-OSC32_IN-Pad3)") (class "Default")
      (node (ref "U1") (pin "3") (pinfunction "PC14-OSC32_IN_3") (pintype "unspecified+no_connect"))
    )
    (net (code "80") (name "unconnected-(U1-PC15-OSC32_OUT-Pad4)") (class "Default")
      (node (ref "U1") (pin "4") (pinfunction "PC15-OSC32_OUT_4") (pintype "unspecified+no_connect"))
    )
    (net (code "81") (name "unconnected-(U3-ANT-Pad19)") (class "Default")
      (node (ref "U3") (pin "19") (pinfunction "ANT_19") (pintype "input+no_connect"))
    )
    (net (code "82") (name "unconnected-(U3-AUX-Pad5)") (class "Default")
      (node (ref "U3") (pin "5") (pinfunction "AUX_5") (pintype "input+no_connect"))
    )
    (net (code "83") (name "unconnected-(U3-NC-Pad8)") (class "Default")
      (node (ref "U3") (pin "8") (pinfunction "NC_8") (pintype "input+no_connect"))
    )
    (net (code "84") (name "unconnected-(U3-NC-Pad9)") (class "Default")
      (node (ref "U3") (pin "9") (pinfunction "NC_9") (pintype "input+no_connect"))
    )
    (net (code "85") (name "unconnected-(U3-NC-Pad10)") (class "Default")
      (node (ref "U3") (pin "10") (pinfunction "NC_10") (pintype "input+no_connect"))
    )
    (net (code "86") (name "unconnected-(U3-NC-Pad11)") (class "Default")
      (node (ref "U3") (pin "11") (pinfunction "NC_11") (pintype "input+no_connect"))
    )
    (net (code "87") (name "unconnected-(U3-NC-Pad12)") (class "Default")
      (node (ref "U3") (pin "12") (pinfunction "NC_12") (pintype "input+no_connect"))
    )
    (net (code "88") (name "unconnected-(U3-NC-Pad13)") (class "Default")
      (node (ref "U3") (pin "13") (pinfunction "NC_13") (pintype "input+no_connect"))
    )
    (net (code "89") (name "unconnected-(U3-NC-Pad14)") (class "Default")
      (node (ref "U3") (pin "14") (pinfunction "NC_14") (pintype "input+no_connect"))
    )
    (net (code "90") (name "unconnected-(U3-NC-Pad15)") (class "Default")
      (node (ref "U3") (pin "15") (pinfunction "NC_15") (pintype "input+no_connect"))
    )
    (net (code "91") (name "unconnected-(U3-NC-Pad16)") (class "Default")
      (node (ref "U3") (pin "16") (pinfunction "NC_16") (pintype "input+no_connect"))
    )
    (net (code "92") (name "unconnected-(U3-NC-Pad17)") (class "Default")
      (node (ref "U3") (pin "17") (pinfunction "NC_17") (pintype "input+no_connect"))
    )
    (net (code "93") (name "unconnected-(U3-NC-Pad21)") (class "Default")
      (node (ref "U3") (pin "21") (pinfunction "NC_21") (pintype "input+no_connect"))
    )
    (net (code "94") (name "unconnected-(U3-NC-Pad22)") (class "Default")
      (node (ref "U3") (pin "22") (pinfunction "NC_22") (pintype "input+no_connect"))
    )
    (net (code "95") (name "unconnected-(U3-NC-Pad23)") (class "Default")
      (node (ref "U3") (pin "23") (pinfunction "NC_23") (pintype "input+no_connect"))
    )
    (net (code "96") (name "unconnected-(U3-NC-Pad24)") (class "Default")
      (node (ref "U3") (pin "24") (pinfunction "NC_24") (pintype "input+no_connect"))
    )
    (net (code "97") (name "unconnected-(U3-NC-Pad25)") (class "Default")
      (node (ref "U3") (pin "25") (pinfunction "NC_25") (pintype "input+no_connect"))
    )
    (net (code "98") (name "unconnected-(U3-NC-Pad26)") (class "Default")
      (node (ref "U3") (pin "26") (pinfunction "NC_26") (pintype "input+no_connect"))
    )
    (net (code "99") (name "unconnected-(U3-NC-Pad27)") (class "Default")
      (node (ref "U3") (pin "27") (pinfunction "NC_27") (pintype "input+no_connect"))
    )
    (net (code "100") (name "unconnected-(U3-NC-Pad28)") (class "Default")
      (node (ref "U3") (pin "28") (pinfunction "NC_28") (pintype "input+no_connect"))
    )
    (net (code "101") (name "unconnected-(U3-NC-Pad29)") (class "Default")
      (node (ref "U3") (pin "29") (pinfunction "NC_29") (pintype "input+no_connect"))
    )
    (net (code "102") (name "unconnected-(U3-NC-Pad30)") (class "Default")
      (node (ref "U3") (pin "30") (pinfunction "NC_30") (pintype "input+no_connect"))
    )
    (net (code "103") (name "unconnected-(U3-NC-Pad31)") (class "Default")
      (node (ref "U3") (pin "31") (pinfunction "NC_31") (pintype "input+no_connect"))
    )
    (net (code "104") (name "unconnected-(U3-NC-Pad32)") (class "Default")
      (node (ref "U3") (pin "32") (pinfunction "NC_32") (pintype "input+no_connect"))
    )
    (net (code "105") (name "unconnected-(U3-NC-Pad33)") (class "Default")
      (node (ref "U3") (pin "33") (pinfunction "NC_33") (pintype "input+no_connect"))
    )
    (net (code "106") (name "unconnected-(U3-NC-Pad37)") (class "Default")
      (node (ref "U3") (pin "37") (pinfunction "NC_37") (pintype "input+no_connect"))
    )
    (net (code "107") (name "unconnected-(U3-NC-Pad38)") (class "Default")
      (node (ref "U3") (pin "38") (pinfunction "NC_38") (pintype "input+no_connect"))
    )
    (net (code "108") (name "unconnected-(U3-NC-Pad39)") (class "Default")
      (node (ref "U3") (pin "39") (pinfunction "NC_39") (pintype "input+no_connect"))
    )
    (net (code "109") (name "unconnected-(U3-NC-Pad40)") (class "Default")
      (node (ref "U3") (pin "40") (pinfunction "NC_40") (pintype "input+no_connect"))
    )
    (net (code "110") (name "unconnected-(U3-NRST-Pad35)") (class "Default")
      (node (ref "U3") (pin "35") (pinfunction "NRST_35") (pintype "input+no_connect"))
    )
    (net (code "111") (name "unconnected-(U3-SWCLK-Pad34)") (class "Default")
      (node (ref "U3") (pin "34") (pinfunction "SWCLK_34") (pintype "input+no_connect"))
    )
    (net (code "112") (name "unconnected-(U3-SWDIO-Pad36)") (class "Default")
      (node (ref "U3") (pin "36") (pinfunction "SWDIO_36") (pintype "input+no_connect"))
    )
    (net (code "113") (name "unconnected-(U5-BYP-Pad4)") (class "Default")
      (node (ref "U5") (pin "4") (pinfunction "BYP_4") (pintype "input+no_connect"))
    )
    (net (code "114") (name "unconnected-(U14-ANT-Pad19)") (class "Default")
      (node (ref "U14") (pin "19") (pinfunction "ANT_19") (pintype "input+no_connect"))
    )
    (net (code "115") (name "unconnected-(U14-AUX-Pad5)") (class "Default")
      (node (ref "U14") (pin "5") (pinfunction "AUX_5") (pintype "input+no_connect"))
    )
    (net (code "116") (name "unconnected-(U14-NC-Pad8)") (class "Default")
      (node (ref "U14") (pin "8") (pinfunction "NC_8") (pintype "input+no_connect"))
    )
    (net (code "117") (name "unconnected-(U14-NC-Pad9)") (class "Default")
      (node (ref "U14") (pin "9") (pinfunction "NC_9") (pintype "input+no_connect"))
    )
    (net (code "118") (name "unconnected-(U14-NC-Pad10)") (class "Default")
      (node (ref "U14") (pin "10") (pinfunction "NC_10") (pintype "input+no_connect"))
    )
    (net (code "119") (name "unconnected-(U14-NC-Pad11)") (class "Default")
      (node (ref "U14") (pin "11") (pinfunction "NC_11") (pintype "input+no_connect"))
    )
    (net (code "120") (name "unconnected-(U14-NC-Pad12)") (class "Default")
      (node (ref "U14") (pin "12") (pinfunction "NC_12") (pintype "input+no_connect"))
    )
    (net (code "121") (name "unconnected-(U14-NC-Pad13)") (class "Default")
      (node (ref "U14") (pin "13") (pinfunction "NC_13") (pintype "input+no_connect"))
    )
    (net (code "122") (name "unconnected-(U14-NC-Pad14)") (class "Default")
      (node (ref "U14") (pin "14") (pinfunction "NC_14") (pintype "input+no_connect"))
    )
    (net (code "123") (name "unconnected-(U14-NC-Pad15)") (class "Default")
      (node (ref "U14") (pin "15") (pinfunction "NC_15") (pintype "input+no_connect"))
    )
    (net (code "124") (name "unconnected-(U14-NC-Pad16)") (class "Default")
      (node (ref "U14") (pin "16") (pinfunction "NC_16") (pintype "input+no_connect"))
    )
    (net (code "125") (name "unconnected-(U14-NC-Pad17)") (class "Default")
      (node (ref "U14") (pin "17") (pinfunction "NC_17") (pintype "input+no_connect"))
    )
    (net (code "126") (name "unconnected-(U14-NC-Pad21)") (class "Default")
      (node (ref "U14") (pin "21") (pinfunction "NC_21") (pintype "input+no_connect"))
    )
    (net (code "127") (name "unconnected-(U14-NC-Pad22)") (class "Default")
      (node (ref "U14") (pin "22") (pinfunction "NC_22") (pintype "input+no_connect"))
    )
    (net (code "128") (name "unconnected-(U14-NC-Pad23)") (class "Default")
      (node (ref "U14") (pin "23") (pinfunction "NC_23") (pintype "input+no_connect"))
    )
    (net (code "129") (name "unconnected-(U14-NC-Pad24)") (class "Default")
      (node (ref "U14") (pin "24") (pinfunction "NC_24") (pintype "input+no_connect"))
    )
    (net (code "130") (name "unconnected-(U14-NC-Pad25)") (class "Default")
      (node (ref "U14") (pin "25") (pinfunction "NC_25") (pintype "input+no_connect"))
    )
    (net (code "131") (name "unconnected-(U14-NC-Pad26)") (class "Default")
      (node (ref "U14") (pin "26") (pinfunction "NC_26") (pintype "input+no_connect"))
    )
    (net (code "132") (name "unconnected-(U14-NC-Pad27)") (class "Default")
      (node (ref "U14") (pin "27") (pinfunction "NC_27") (pintype "input+no_connect"))
    )
    (net (code "133") (name "unconnected-(U14-NC-Pad28)") (class "Default")
      (node (ref "U14") (pin "28") (pinfunction "NC_28") (pintype "input+no_connect"))
    )
    (net (code "134") (name "unconnected-(U14-NC-Pad29)") (class "Default")
      (node (ref "U14") (pin "29") (pinfunction "NC_29") (pintype "input+no_connect"))
    )
    (net (code "135") (name "unconnected-(U14-NC-Pad30)") (class "Default")
      (node (ref "U14") (pin "30") (pinfunction "NC_30") (pintype "input+no_connect"))
    )
    (net (code "136") (name "unconnected-(U14-NC-Pad31)") (class "Default")
      (node (ref "U14") (pin "31") (pinfunction "NC_31") (pintype "input+no_connect"))
    )
    (net (code "137") (name "unconnected-(U14-NC-Pad32)") (class "Default")
      (node (ref "U14") (pin "32") (pinfunction "NC_32") (pintype "input+no_connect"))
    )
    (net (code "138") (name "unconnected-(U14-NC-Pad33)") (class "Default")
      (node (ref "U14") (pin "33") (pinfunction "NC_33") (pintype "input+no_connect"))
    )
    (net (code "139") (name "unconnected-(U14-NC-Pad37)") (class "Default")
      (node (ref "U14") (pin "37") (pinfunction "NC_37") (pintype "input+no_connect"))
    )
    (net (code "140") (name "unconnected-(U14-NC-Pad38)") (class "Default")
      (node (ref "U14") (pin "38") (pinfunction "NC_38") (pintype "input+no_connect"))
    )
    (net (code "141") (name "unconnected-(U14-NC-Pad39)") (class "Default")
      (node (ref "U14") (pin "39") (pinfunction "NC_39") (pintype "input+no_connect"))
    )
    (net (code "142") (name "unconnected-(U14-NC-Pad40)") (class "Default")
      (node (ref "U14") (pin "40") (pinfunction "NC_40") (pintype "input+no_connect"))
    )
    (net (code "143") (name "unconnected-(U14-NRST-Pad35)") (class "Default")
      (node (ref "U14") (pin "35") (pinfunction "NRST_35") (pintype "input+no_connect"))
    )
    (net (code "144") (name "unconnected-(U14-SWCLK-Pad34)") (class "Default")
      (node (ref "U14") (pin "34") (pinfunction "SWCLK_34") (pintype "input+no_connect"))
    )
    (net (code "145") (name "unconnected-(U14-SWDIO-Pad36)") (class "Default")
      (node (ref "U14") (pin "36") (pinfunction "SWDIO_36") (pintype "input+no_connect"))
    )
    (net (code "146") (name "unconnected-(U16-CTS#-Pad9)") (class "Default")
      (node (ref "U16") (pin "9") (pinfunction "CTS#_9") (pintype "unspecified+no_connect"))
    )
    (net (code "147") (name "unconnected-(U16-DCD#-Pad12)") (class "Default")
      (node (ref "U16") (pin "12") (pinfunction "DCD#_12") (pintype "unspecified+no_connect"))
    )
    (net (code "148") (name "unconnected-(U16-DSR#-Pad10)") (class "Default")
      (node (ref "U16") (pin "10") (pinfunction "DSR#_10") (pintype "unspecified+no_connect"))
    )
    (net (code "149") (name "unconnected-(U16-DTR#-Pad13)") (class "Default")
      (node (ref "U16") (pin "13") (pinfunction "DTR#_13") (pintype "unspecified+no_connect"))
    )
    (net (code "150") (name "unconnected-(U16-R232-Pad15)") (class "Default")
      (node (ref "U16") (pin "15") (pinfunction "R232_15") (pintype "unspecified+no_connect"))
    )
    (net (code "151") (name "unconnected-(U16-RI#-Pad11)") (class "Default")
      (node (ref "U16") (pin "11") (pinfunction "RI#_11") (pintype "unspecified+no_connect"))
    )
    (net (code "152") (name "unconnected-(U16-RTS#-Pad14)") (class "Default")
      (node (ref "U16") (pin "14") (pinfunction "RTS#_14") (pintype "unspecified+no_connect"))
    )
    (net (code "153") (name "unconnected-(U17-Pad1)") (class "Default")
      (node (ref "U17") (pin "1") (pinfunction "1_1") (pintype "unspecified+no_connect"))
    )
    (net (code "154") (name "unconnected-(U17-Pad2)") (class "Default")
      (node (ref "U17") (pin "2") (pinfunction "2_2") (pintype "unspecified+no_connect"))
    )
    (net (code "155") (name "unconnected-(U17-Pad6)") (class "Default")
      (node (ref "U17") (pin "6") (pinfunction "6_6") (pintype "unspecified+no_connect"))
    )
    (net (code "156") (name "unconnected-(U17-Pad7)") (class "Default")
      (node (ref "U17") (pin "7") (pinfunction "7_7") (pintype "unspecified+no_connect"))
    )
    (net (code "157") (name "unconnected-(U17-Pad8)") (class "Default")
      (node (ref "U17") (pin "8") (pinfunction "8_8") (pintype "unspecified+no_connect"))
    )
    (net (code "158") (name "unconnected-(U17-Pad9)") (class "Default")
      (node (ref "U17") (pin "9") (pinfunction "9_9") (pintype "unspecified+no_connect"))
    )
    (net (code "159") (name "unconnected-(U17-Pad10)") (class "Default")
      (node (ref "U17") (pin "10") (pinfunction "10_10") (pintype "unspecified+no_connect"))
    )
    (net (code "160") (name "unconnected-(U17-Pad20)") (class "Default")
      (node (ref "U17") (pin "20") (pinfunction "20_20") (pintype "unspecified+no_connect"))
    )
    (net (code "161") (name "unconnected-(U17-Pad21)") (class "Default")
      (node (ref "U17") (pin "21") (pinfunction "21_21") (pintype "unspecified+no_connect"))
    )
    (net (code "162") (name "unconnected-(U17-Pad22)") (class "Default")
      (node (ref "U17") (pin "22") (pinfunction "22_22") (pintype "unspecified+no_connect"))
    )
    (net (code "163") (name "unconnected-(U17-Pad23)") (class "Default")
      (node (ref "U17") (pin "23") (pinfunction "23_23") (pintype "unspecified+no_connect"))
    )
    (net (code "164") (name "unconnected-(U17-Pad24)") (class "Default")
      (node (ref "U17") (pin "24") (pinfunction "24_24") (pintype "unspecified+no_connect"))
    )
    (net (code "165") (name "unconnected-(USB2-CC1-Pad4)") (class "Default")
      (node (ref "USB2") (pin "4") (pinfunction "CC1_4") (pintype "unspecified+no_connect"))
    )
    (net (code "166") (name "unconnected-(USB2-CC2-Pad10)") (class "Default")
      (node (ref "USB2") (pin "10") (pinfunction "CC2_10") (pintype "unspecified+no_connect"))
    )
    (net (code "167") (name "unconnected-(USB2-SBU1-Pad9)") (class "Default")
      (node (ref "USB2") (pin "9") (pinfunction "SBU1_9") (pintype "unspecified+no_connect"))
    )
    (net (code "168") (name "unconnected-(USB2-SBU2-Pad3)") (class "Default")
      (node (ref "USB2") (pin "3") (pinfunction "SBU2_3") (pintype "unspecified+no_connect"))
    )
    (net (code "169") (name "unconnected-(USB2-SHELL-Pad13)") (class "Default")
      (node (ref "USB2") (pin "13") (pinfunction "SHELL_13") (pintype "unspecified+no_connect"))
    )
    (net (code "170") (name "unconnected-(USB2-SHELL-Pad14)") (class "Default")
      (node (ref "USB2") (pin "14") (pinfunction "SHELL_14") (pintype "unspecified+no_connect"))
    )
    (net (code "171") (name "unconnected-(X1-GND-Pad2)") (class "Default")
      (node (ref "X1") (pin "2") (pinfunction "GND_2") (pintype "input+no_connect"))
    )
    (net (code "172") (name "unconnected-(X1-GND-Pad4)") (class "Default")
      (node (ref "X1") (pin "4") (pinfunction "GND_4") (pintype "input+no_connect"))
    )
  )
)
